# PROYECT2019.net
KiCad netlist of a schematic drawn in EAGLE
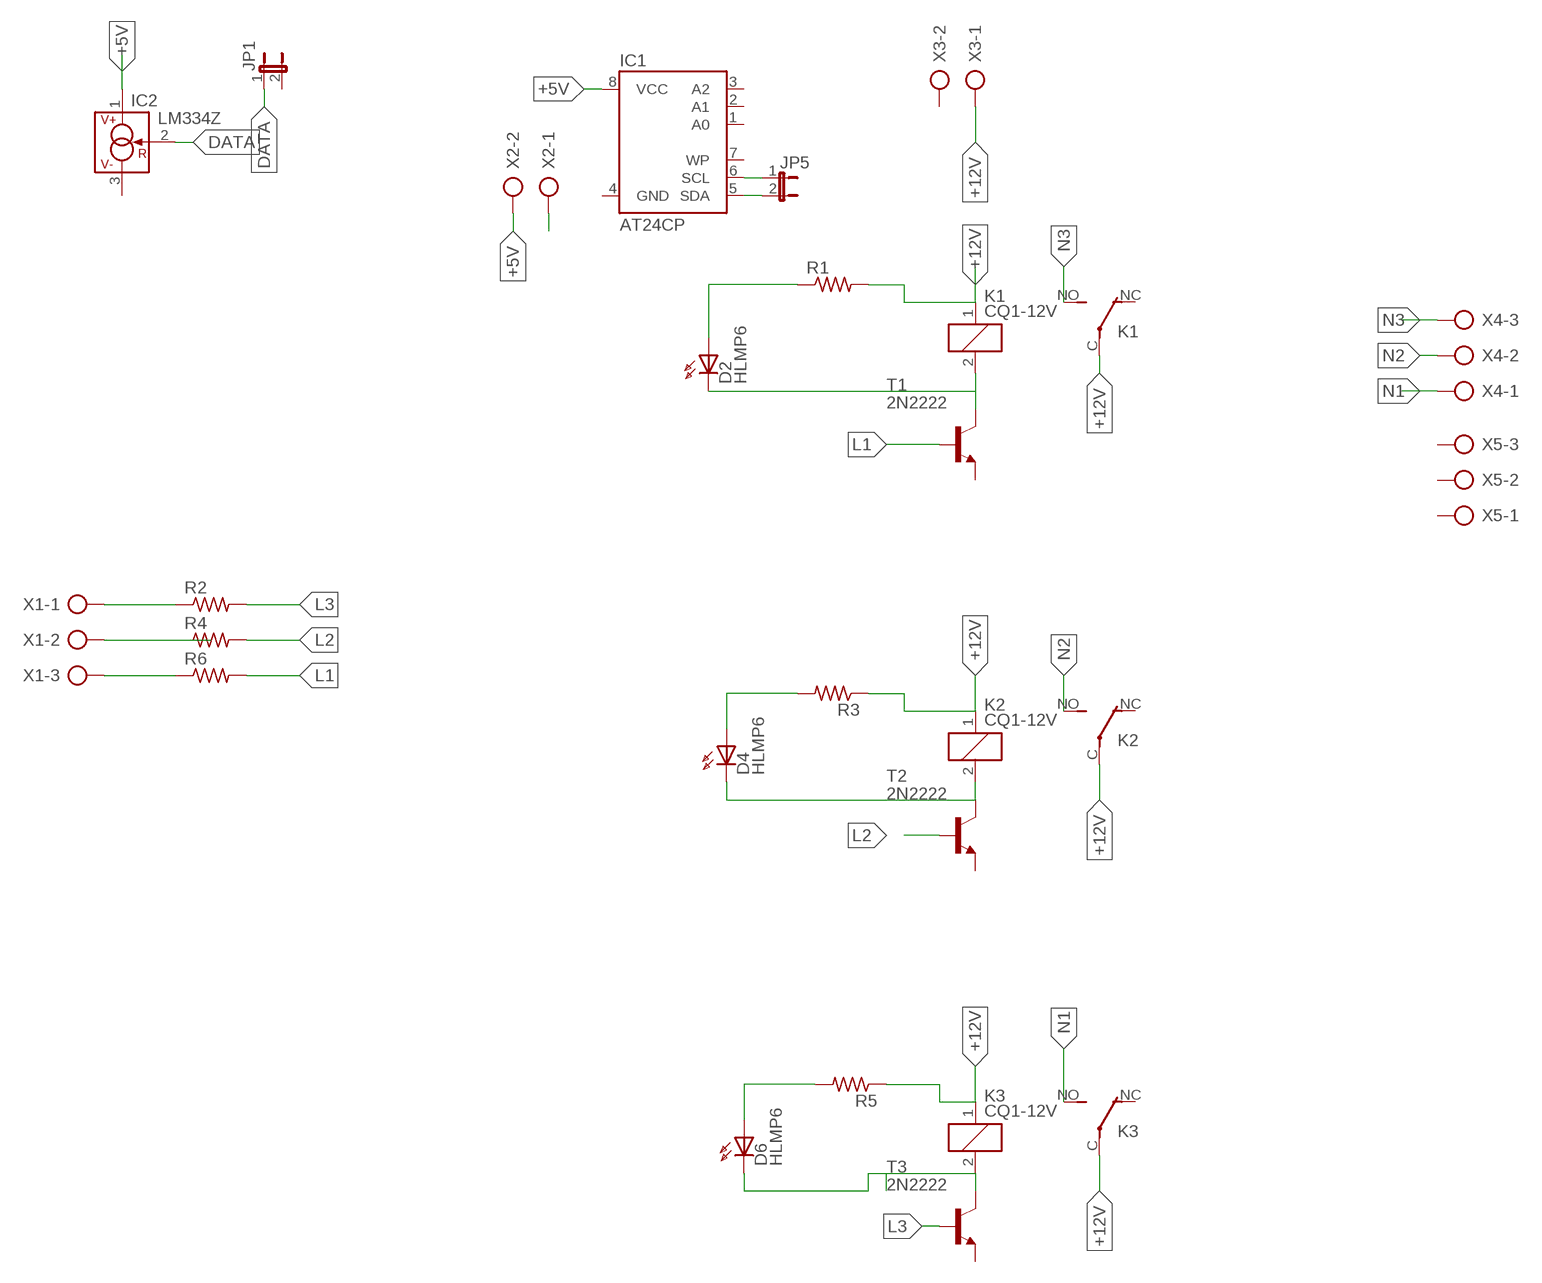
[diagram p0: schematic, sheet 1]

(export (version "E")
  (design (tool "Eeschema 10.0.6"))
  (components
    (comp (ref "D2")
      (value "HLMP6")
      (footprint "eagle-import:HLMP6")
      (fields (field (name "MF") "AGILENT TECHNOLOGIES") (field (name "MPN") "HLMP-6500"))
      (libsource (lib "eagle-import") (part "HLMP6"))
    )
    (comp (ref "D4")
      (value "HLMP6")
      (footprint "eagle-import:HLMP6")
      (fields (field (name "MF") "AGILENT TECHNOLOGIES") (field (name "MPN") "HLMP-6500"))
      (libsource (lib "eagle-import") (part "HLMP6"))
    )
    (comp (ref "D6")
      (value "HLMP6")
      (footprint "eagle-import:HLMP6")
      (fields (field (name "MF") "AGILENT TECHNOLOGIES") (field (name "MPN") "HLMP-6500"))
      (libsource (lib "eagle-import") (part "HLMP6"))
    )
    (comp (ref "IC1")
      (value "AT24CP")
      (footprint "eagle-import:DIL08")
      (fields (field (name "MPN") "AT24C1024BW-SH-B"))
      (libsource (lib "eagle-import") (part "AT24CP"))
    )
    (comp (ref "IC2")
      (value "LM334Z")
      (footprint "eagle-import:TO92")
      (libsource (lib "eagle-import") (part "LM34Z3"))
    )
    (comp (ref "JP1")
      (value "JP1E")
      (footprint "eagle-import:JP1")
      (libsource (lib "eagle-import") (part "JP1E"))
    )
    (comp (ref "JP5")
      (value "JP1E")
      (footprint "eagle-import:JP1")
      (libsource (lib "eagle-import") (part "JP1E"))
    )
    (comp (ref "K1")
      (value "CQ1-12V")
      (footprint "eagle-import:CQ1")
      (libsource (lib "eagle-import") (part "CQ1-12V"))
    )
    (comp (ref "K2")
      (value "CQ1-12V")
      (footprint "eagle-import:CQ1")
      (libsource (lib "eagle-import") (part "CQ1-12V"))
    )
    (comp (ref "K3")
      (value "CQ1-12V")
      (footprint "eagle-import:CQ1")
      (libsource (lib "eagle-import") (part "CQ1-12V"))
    )
    (comp (ref "R1")
      (value "R-US_0207/12")
      (footprint "eagle-import:0207_12")
      (libsource (lib "eagle-import") (part "R-US_0207/12"))
    )
    (comp (ref "R2")
      (value "R-US_0207/12")
      (footprint "eagle-import:0207_12")
      (libsource (lib "eagle-import") (part "R-US_0207/12"))
    )
    (comp (ref "R3")
      (value "R-US_0207/12")
      (footprint "eagle-import:0207_12")
      (libsource (lib "eagle-import") (part "R-US_0207/12"))
    )
    (comp (ref "R4")
      (value "R-US_0207/12")
      (footprint "eagle-import:0207_12")
      (libsource (lib "eagle-import") (part "R-US_0207/12"))
    )
    (comp (ref "R5")
      (value "R-US_0207/12")
      (footprint "eagle-import:0207_12")
      (libsource (lib "eagle-import") (part "R-US_0207/12"))
    )
    (comp (ref "R6")
      (value "R-US_0207/12")
      (footprint "eagle-import:0207_12")
      (libsource (lib "eagle-import") (part "R-US_0207/12"))
    )
    (comp (ref "T1")
      (value "2N2222")
      (footprint "eagle-import:TO18")
      (libsource (lib "eagle-import") (part "2N2222"))
    )
    (comp (ref "T2")
      (value "2N2222")
      (footprint "eagle-import:TO18")
      (libsource (lib "eagle-import") (part "2N2222"))
    )
    (comp (ref "T3")
      (value "2N2222")
      (footprint "eagle-import:TO18")
      (libsource (lib "eagle-import") (part "2N2222"))
    )
    (comp (ref "X1")
      (value "AK300/3")
      (footprint "eagle-import:AK300_3")
      (libsource (lib "eagle-import") (part "AK300/3"))
    )
    (comp (ref "X2")
      (value "AK300/2")
      (footprint "eagle-import:AK300_2")
      (libsource (lib "eagle-import") (part "AK300/2"))
    )
    (comp (ref "X3")
      (value "AK300/2")
      (footprint "eagle-import:AK300_2")
      (libsource (lib "eagle-import") (part "AK300/2"))
    )
    (comp (ref "X4")
      (value "AK300/3")
      (footprint "eagle-import:AK300_3")
      (libsource (lib "eagle-import") (part "AK300/3"))
    )
    (comp (ref "X5")
      (value "AK300/3")
      (footprint "eagle-import:AK300_3")
      (libsource (lib "eagle-import") (part "AK300/3"))
    )
  )
  (nets
    (net (code "1") (name "+5V") (class "Default")
      (node (ref "IC1") (pin "8") (pinfunction "VCC_8") (pintype "power_in"))
      (node (ref "IC2") (pin "1") (pinfunction "V+_1") (pintype "passive"))
      (node (ref "X2") (pin "2") (pinfunction "KL_2") (pintype "passive"))
    )
    (net (code "2") (name "+12V") (class "Default")
      (node (ref "K1") (pin "1") (pinfunction "1_1") (pintype "passive"))
      (node (ref "K1") (pin "C") (pinfunction "P_C") (pintype "passive"))
      (node (ref "K2") (pin "1") (pinfunction "1_1") (pintype "passive"))
      (node (ref "K2") (pin "C") (pinfunction "P_C") (pintype "passive"))
      (node (ref "K3") (pin "1") (pinfunction "1_1") (pintype "passive"))
      (node (ref "K3") (pin "C") (pinfunction "P_C") (pintype "passive"))
      (node (ref "R1") (pin "2") (pinfunction "2_2") (pintype "passive"))
      (node (ref "R3") (pin "1") (pinfunction "1_1") (pintype "passive"))
      (node (ref "R5") (pin "1") (pinfunction "1_1") (pintype "passive"))
      (node (ref "X3") (pin "1") (pinfunction "KL_1") (pintype "passive"))
    )
    (net (code "3") (name "/GND") (class "Default")
      (node (ref "IC1") (pin "4") (pinfunction "GND_4") (pintype "power_in"))
    )
    (net (code "4") (name "DATA") (class "Default")
      (node (ref "IC2") (pin "2") (pinfunction "R_2") (pintype "passive"))
      (node (ref "JP1") (pin "1") (pinfunction "1_1") (pintype "passive"))
    )
    (net (code "5") (name "L1") (class "Default")
      (node (ref "R6") (pin "2") (pinfunction "2_2") (pintype "passive"))
      (node (ref "T1") (pin "2") (pinfunction "B_2") (pintype "passive"))
    )
    (net (code "6") (name "L2") (class "Default")
      (node (ref "R4") (pin "2") (pinfunction "2_2") (pintype "passive"))
      (node (ref "T2") (pin "2") (pinfunction "B_2") (pintype "passive"))
    )
    (net (code "7") (name "L3") (class "Default")
      (node (ref "R2") (pin "2") (pinfunction "2_2") (pintype "passive"))
      (node (ref "T3") (pin "2") (pinfunction "B_2") (pintype "passive"))
    )
    (net (code "8") (name "N1") (class "Default")
      (node (ref "K3") (pin "NO") (pinfunction "S_NO") (pintype "passive"))
      (node (ref "X4") (pin "1") (pinfunction "KL_1") (pintype "passive"))
    )
    (net (code "9") (name "N2") (class "Default")
      (node (ref "K2") (pin "NO") (pinfunction "S_NO") (pintype "passive"))
      (node (ref "X4") (pin "2") (pinfunction "KL_2") (pintype "passive"))
    )
    (net (code "10") (name "N3") (class "Default")
      (node (ref "K1") (pin "NO") (pinfunction "S_NO") (pintype "passive"))
      (node (ref "X4") (pin "3") (pinfunction "KL_3") (pintype "passive"))
    )
    (net (code "11") (name "Net-(D2-PadA)") (class "Default")
      (node (ref "D2") (pin "A") (pinfunction "A_A") (pintype "passive"))
      (node (ref "R1") (pin "1") (pinfunction "1_1") (pintype "passive"))
    )
    (net (code "12") (name "Net-(D4-PadA)") (class "Default")
      (node (ref "D4") (pin "A") (pinfunction "A_A") (pintype "passive"))
      (node (ref "R3") (pin "2") (pinfunction "2_2") (pintype "passive"))
    )
    (net (code "13") (name "Net-(D6-PadA)") (class "Default")
      (node (ref "D6") (pin "A") (pinfunction "A_A") (pintype "passive"))
      (node (ref "R5") (pin "2") (pinfunction "2_2") (pintype "passive"))
    )
    (net (code "14") (name "Net-(IC1-SCL)") (class "Default")
      (node (ref "IC1") (pin "6") (pinfunction "SCL_6") (pintype "bidirectional"))
      (node (ref "JP5") (pin "1") (pinfunction "1_1") (pintype "passive"))
    )
    (net (code "15") (name "Net-(IC1-SDA)") (class "Default")
      (node (ref "IC1") (pin "5") (pinfunction "SDA_5") (pintype "bidirectional"))
      (node (ref "JP5") (pin "2") (pinfunction "2_2") (pintype "passive"))
    )
    (net (code "16") (name "Net-(T1-C)") (class "Default")
      (node (ref "D2") (pin "K") (pinfunction "K_K") (pintype "passive"))
      (node (ref "K1") (pin "2") (pinfunction "2_2") (pintype "passive"))
      (node (ref "T1") (pin "3") (pinfunction "C_3") (pintype "passive"))
    )
    (net (code "17") (name "Net-(T2-C)") (class "Default")
      (node (ref "D4") (pin "K") (pinfunction "K_K") (pintype "passive"))
      (node (ref "K2") (pin "2") (pinfunction "2_2") (pintype "passive"))
      (node (ref "T2") (pin "3") (pinfunction "C_3") (pintype "passive"))
    )
    (net (code "18") (name "Net-(T3-C)") (class "Default")
      (node (ref "D6") (pin "K") (pinfunction "K_K") (pintype "passive"))
      (node (ref "K3") (pin "2") (pinfunction "2_2") (pintype "passive"))
      (node (ref "T3") (pin "3") (pinfunction "C_3") (pintype "passive"))
    )
    (net (code "19") (name "Net-(X1A-KL)") (class "Default")
      (node (ref "R2") (pin "1") (pinfunction "1_1") (pintype "passive"))
      (node (ref "X1") (pin "1") (pinfunction "KL_1") (pintype "passive"))
    )
    (net (code "20") (name "Net-(X1B-KL)") (class "Default")
      (node (ref "R4") (pin "1") (pinfunction "1_1") (pintype "passive"))
      (node (ref "X1") (pin "2") (pinfunction "KL_2") (pintype "passive"))
    )
    (net (code "21") (name "Net-(X1C-KL)") (class "Default")
      (node (ref "R6") (pin "1") (pinfunction "1_1") (pintype "passive"))
      (node (ref "X1") (pin "3") (pinfunction "KL_3") (pintype "passive"))
    )
    (net (code "22") (name "unconnected-(IC1-A0-Pad1)") (class "Default")
      (node (ref "IC1") (pin "1") (pinfunction "A0_1") (pintype "input"))
    )
    (net (code "23") (name "unconnected-(IC1-A1-Pad2)") (class "Default")
      (node (ref "IC1") (pin "2") (pinfunction "A1_2") (pintype "input"))
    )
    (net (code "24") (name "unconnected-(IC1-A2-Pad3)") (class "Default")
      (node (ref "IC1") (pin "3") (pinfunction "A2_3") (pintype "input"))
    )
    (net (code "25") (name "unconnected-(IC1-WP-Pad7)") (class "Default")
      (node (ref "IC1") (pin "7") (pinfunction "WP_7") (pintype "input"))
    )
    (net (code "26") (name "unconnected-(IC2-V--Pad3)") (class "Default")
      (node (ref "IC2") (pin "3") (pinfunction "V-_3") (pintype "passive"))
    )
    (net (code "27") (name "unconnected-(JP1-Pad2)") (class "Default")
      (node (ref "JP1") (pin "2") (pinfunction "2_2") (pintype "passive"))
    )
    (net (code "28") (name "unconnected-(K1B-O-PadNC)") (class "Default")
      (node (ref "K1") (pin "NC") (pinfunction "O_NC") (pintype "passive"))
    )
    (net (code "29") (name "unconnected-(K2B-O-PadNC)") (class "Default")
      (node (ref "K2") (pin "NC") (pinfunction "O_NC") (pintype "passive"))
    )
    (net (code "30") (name "unconnected-(K3B-O-PadNC)") (class "Default")
      (node (ref "K3") (pin "NC") (pinfunction "O_NC") (pintype "passive"))
    )
    (net (code "31") (name "unconnected-(T1-E-Pad1)") (class "Default")
      (node (ref "T1") (pin "1") (pinfunction "E_1") (pintype "passive"))
    )
    (net (code "32") (name "unconnected-(T2-E-Pad1)") (class "Default")
      (node (ref "T2") (pin "1") (pinfunction "E_1") (pintype "passive"))
    )
    (net (code "33") (name "unconnected-(T3-E-Pad1)") (class "Default")
      (node (ref "T3") (pin "1") (pinfunction "E_1") (pintype "passive"))
    )
    (net (code "34") (name "unconnected-(X2A-KL-Pad1)") (class "Default")
      (node (ref "X2") (pin "1") (pinfunction "KL_1") (pintype "passive"))
    )
    (net (code "35") (name "unconnected-(X3B-KL-Pad2)") (class "Default")
      (node (ref "X3") (pin "2") (pinfunction "KL_2") (pintype "passive"))
    )
    (net (code "36") (name "unconnected-(X5A-KL-Pad1)") (class "Default")
      (node (ref "X5") (pin "1") (pinfunction "KL_1") (pintype "passive"))
    )
    (net (code "37") (name "unconnected-(X5B-KL-Pad2)") (class "Default")
      (node (ref "X5") (pin "2") (pinfunction "KL_2") (pintype "passive"))
    )
    (net (code "38") (name "unconnected-(X5C-KL-Pad3)") (class "Default")
      (node (ref "X5") (pin "3") (pinfunction "KL_3") (pintype "passive"))
    )
  )
)
